# Frogduino.net
KiCad netlist of a schematic drawn in EAGLE
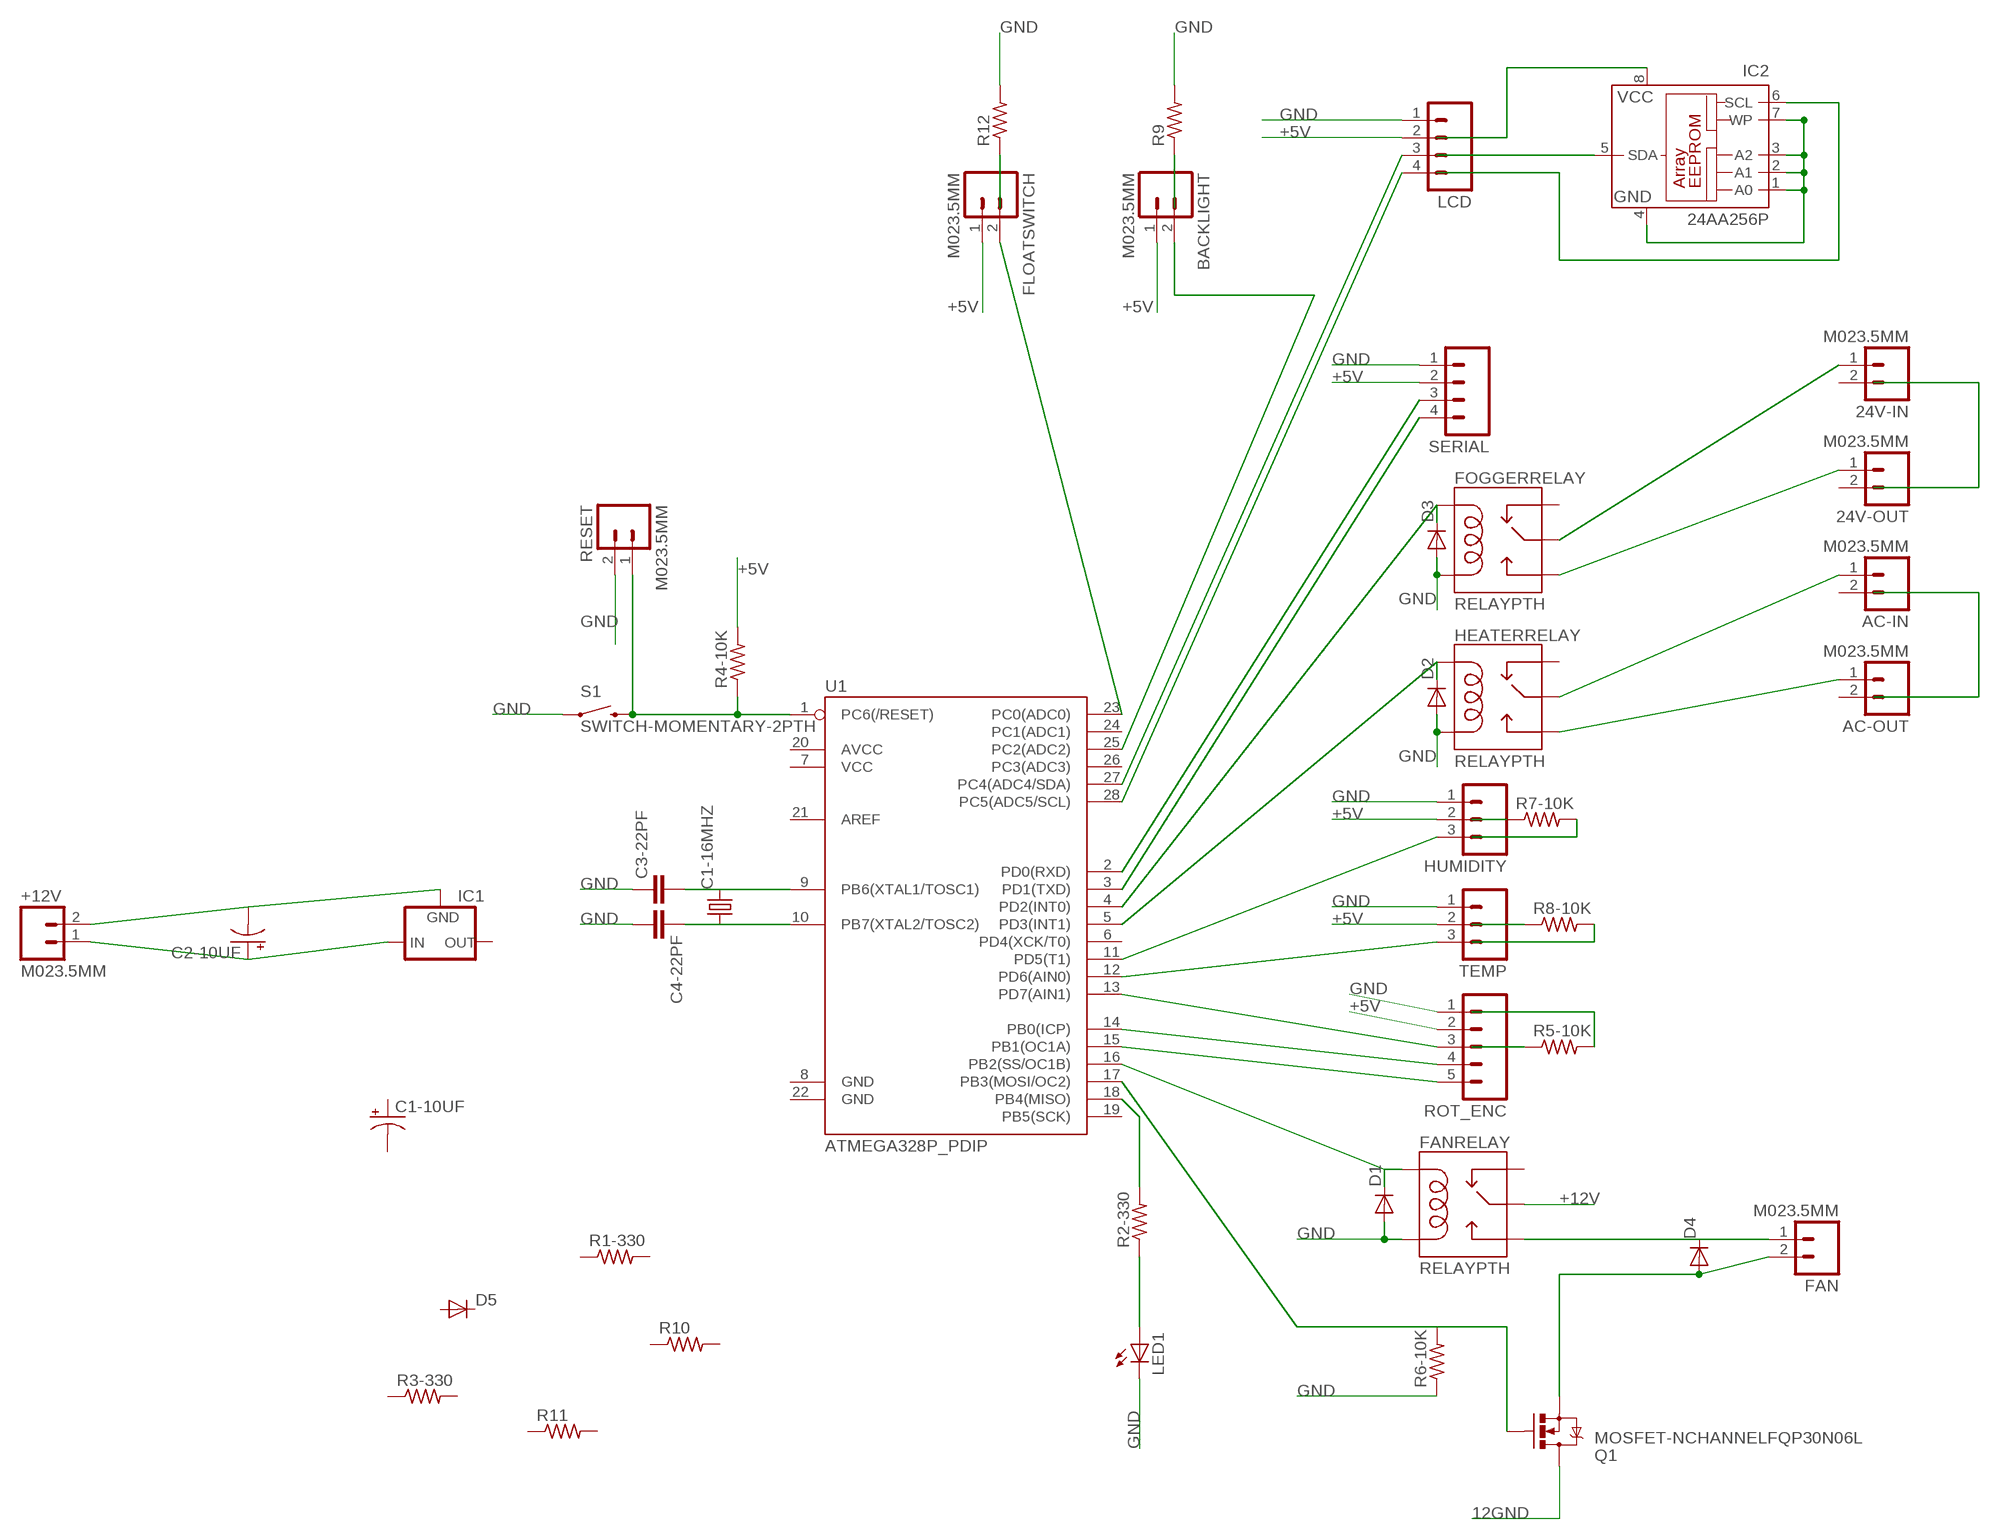
[diagram p0: schematic, sheet 1]

(export (version "E")
  (design (tool "Eeschema 10.0.6"))
  (components
    (comp (ref "+12V")
      (value "M023.5MM")
      (footprint "eagle-import:SCREWTERMINAL-3.5MM-2")
      (libsource (lib "eagle-import") (part "M023.5MM"))
    )
    (comp (ref "24V-IN")
      (value "M023.5MM")
      (footprint "eagle-import:SCREWTERMINAL-3.5MM-2")
      (libsource (lib "eagle-import") (part "M023.5MM"))
    )
    (comp (ref "24V-OUT")
      (value "M023.5MM")
      (footprint "eagle-import:SCREWTERMINAL-3.5MM-2")
      (libsource (lib "eagle-import") (part "M023.5MM"))
    )
    (comp (ref "AC-IN")
      (value "M023.5MM")
      (footprint "eagle-import:SCREWTERMINAL-3.5MM-2")
      (libsource (lib "eagle-import") (part "M023.5MM"))
    )
    (comp (ref "AC-OUT")
      (value "M023.5MM")
      (footprint "eagle-import:SCREWTERMINAL-3.5MM-2")
      (libsource (lib "eagle-import") (part "M023.5MM"))
    )
    (comp (ref "BACKLIGHT")
      (value "M023.5MM")
      (footprint "eagle-import:SCREWTERMINAL-3.5MM-2")
      (libsource (lib "eagle-import") (part "M023.5MM"))
    )
    (comp (ref "C1-10UF")
      (value "CAP_POLPTH2")
      (footprint "eagle-import:CPOL-RADIAL-10UF-25V")
      (libsource (lib "eagle-import") (part "CAP_POLPTH2"))
    )
    (comp (ref "C1-16MHZ")
      (value "CRYSTALHC49US")
      (footprint "eagle-import:HC49US")
      (libsource (lib "eagle-import") (part "CRYSTALHC49US"))
    )
    (comp (ref "C2-10UF")
      (value "CAP_POLPTH2")
      (footprint "eagle-import:CPOL-RADIAL-10UF-25V")
      (libsource (lib "eagle-import") (part "CAP_POLPTH2"))
    )
    (comp (ref "C3-22PF")
      (value "CAPKIT")
      (footprint "eagle-import:CAP-PTH-SMALL-KIT")
      (libsource (lib "eagle-import") (part "CAPKIT"))
    )
    (comp (ref "C4-22PF")
      (value "CAPKIT")
      (footprint "eagle-import:CAP-PTH-SMALL-KIT")
      (libsource (lib "eagle-import") (part "CAPKIT"))
    )
    (comp (ref "D1")
      (value "DIODEPTH")
      (footprint "eagle-import:DIODE-1N4001")
      (libsource (lib "eagle-import") (part "DIODEPTH"))
    )
    (comp (ref "D2")
      (value "DIODEPTH")
      (footprint "eagle-import:DIODE-1N4001")
      (libsource (lib "eagle-import") (part "DIODEPTH"))
    )
    (comp (ref "D3")
      (value "DIODEPTH")
      (footprint "eagle-import:DIODE-1N4001")
      (libsource (lib "eagle-import") (part "DIODEPTH"))
    )
    (comp (ref "D4")
      (value "DIODEPTH")
      (footprint "eagle-import:DIODE-1N4001")
      (libsource (lib "eagle-import") (part "DIODEPTH"))
    )
    (comp (ref "D5")
      (value "DIODEPTH")
      (footprint "eagle-import:DIODE-1N4001")
      (libsource (lib "eagle-import") (part "DIODEPTH"))
    )
    (comp (ref "FAN")
      (value "M023.5MM")
      (footprint "eagle-import:SCREWTERMINAL-3.5MM-2")
      (libsource (lib "eagle-import") (part "M023.5MM"))
    )
    (comp (ref "FANRELAY")
      (value "RELAYPTH")
      (footprint "eagle-import:RELAY-G5Q")
      (libsource (lib "eagle-import") (part "RELAYPTH"))
    )
    (comp (ref "FLOATSWITCH")
      (value "M023.5MM")
      (footprint "eagle-import:SCREWTERMINAL-3.5MM-2")
      (libsource (lib "eagle-import") (part "M023.5MM"))
    )
    (comp (ref "FOGGERRELAY")
      (value "RELAYPTH")
      (footprint "eagle-import:RELAY-G5Q")
      (libsource (lib "eagle-import") (part "RELAYPTH"))
    )
    (comp (ref "HEATERRELAY")
      (value "RELAYPTH")
      (footprint "eagle-import:RELAY-G5Q")
      (libsource (lib "eagle-import") (part "RELAYPTH"))
    )
    (comp (ref "HUMIDITY")
      (value "M03SCREW")
      (footprint "eagle-import:SCREWTERMINAL-3.5MM-3")
      (libsource (lib "eagle-import") (part "M03SCREW"))
    )
    (comp (ref "IC1")
      (value "V_REG_78XX-TO-220")
      (footprint "eagle-import:TO-220-ALT")
      (libsource (lib "eagle-import") (part "V_REG_78XX-TO-220"))
    )
    (comp (ref "IC2")
      (value "24AA256P")
      (footprint "eagle-import:DIL8")
      (fields (field (name "MF") "MICROCHIP") (field (name "MPN") "24AA256-I/P"))
      (libsource (lib "eagle-import") (part "24PAA256"))
    )
    (comp (ref "LCD")
      (value "M04PTH")
      (footprint "eagle-import:1X04")
      (libsource (lib "eagle-import") (part "M04PTH"))
    )
    (comp (ref "LED1")
      (value "LED5MM")
      (footprint "eagle-import:LED5MM")
      (libsource (lib "eagle-import") (part "LED5MM"))
    )
    (comp (ref "Q1")
      (value "MOSFET-NCHANNELFQP30N06L")
      (footprint "eagle-import:TO220V")
      (libsource (lib "eagle-import") (part "MOSFET-NCHANNELFQP30N06L"))
    )
    (comp (ref "R1-330")
      (value "R-US_0204/5")
      (footprint "eagle-import:0204_5")
      (libsource (lib "eagle-import") (part "R-US_0204/5"))
    )
    (comp (ref "R2-330")
      (value "R-US_0204/5")
      (footprint "eagle-import:0204_5")
      (libsource (lib "eagle-import") (part "R-US_0204/5"))
    )
    (comp (ref "R3-330")
      (value "R-US_0204/5")
      (footprint "eagle-import:0204_5")
      (libsource (lib "eagle-import") (part "R-US_0204/5"))
    )
    (comp (ref "R4-10K")
      (value "R-US_0204/5")
      (footprint "eagle-import:0204_5")
      (libsource (lib "eagle-import") (part "R-US_0204/5"))
    )
    (comp (ref "R5-10K")
      (value "R-US_0204/5")
      (footprint "eagle-import:0204_5")
      (libsource (lib "eagle-import") (part "R-US_0204/5"))
    )
    (comp (ref "R6-10K")
      (value "R-US_0204/5")
      (footprint "eagle-import:0204_5")
      (libsource (lib "eagle-import") (part "R-US_0204/5"))
    )
    (comp (ref "R7-10K")
      (value "R-US_0204/5")
      (footprint "eagle-import:0204_5")
      (libsource (lib "eagle-import") (part "R-US_0204/5"))
    )
    (comp (ref "R8-10K")
      (value "R-US_0204/5")
      (footprint "eagle-import:0204_5")
      (libsource (lib "eagle-import") (part "R-US_0204/5"))
    )
    (comp (ref "R9")
      (value "R-US_0204/5")
      (footprint "eagle-import:0204_5")
      (libsource (lib "eagle-import") (part "R-US_0204/5"))
    )
    (comp (ref "R10")
      (value "R-US_0204/5")
      (footprint "eagle-import:0204_5")
      (libsource (lib "eagle-import") (part "R-US_0204/5"))
    )
    (comp (ref "R11")
      (value "R-US_0204/5")
      (footprint "eagle-import:0204_5")
      (libsource (lib "eagle-import") (part "R-US_0204/5"))
    )
    (comp (ref "R12")
      (value "R-US_0204/5")
      (footprint "eagle-import:0204_5")
      (libsource (lib "eagle-import") (part "R-US_0204/5"))
    )
    (comp (ref "RESET")
      (value "M023.5MM")
      (footprint "eagle-import:SCREWTERMINAL-3.5MM-2")
      (libsource (lib "eagle-import") (part "M023.5MM"))
    )
    (comp (ref "ROT_ENC")
      (value "M05PTH")
      (footprint "eagle-import:1X05")
      (libsource (lib "eagle-import") (part "M05PTH"))
    )
    (comp (ref "S1")
      (value "SWITCH-MOMENTARY-2PTH")
      (footprint "eagle-import:TACTILE-PTH")
      (libsource (lib "eagle-import") (part "SWITCH-MOMENTARY-2PTH"))
    )
    (comp (ref "SERIAL")
      (value "M04SCREW")
      (footprint "eagle-import:SCREWTERMINAL-3.5MM-4")
      (libsource (lib "eagle-import") (part "M04SCREW"))
    )
    (comp (ref "TEMP")
      (value "M03SCREW")
      (footprint "eagle-import:SCREWTERMINAL-3.5MM-3")
      (libsource (lib "eagle-import") (part "M03SCREW"))
    )
    (comp (ref "U1")
      (value "ATMEGA328P_PDIP")
      (footprint "eagle-import:DIL28-3")
      (libsource (lib "eagle-import") (part "ATMEGA328P_PDIP"))
    )
  )
  (nets
    (net (code "1") (name "/+5V") (class "Default")
      (node (ref "BACKLIGHT") (pin "1") (pinfunction "1_1") (pintype "passive"))
      (node (ref "FLOATSWITCH") (pin "1") (pinfunction "1_1") (pintype "passive"))
      (node (ref "HUMIDITY") (pin "2") (pinfunction "2_2") (pintype "passive"))
      (node (ref "LCD") (pin "2") (pinfunction "2_2") (pintype "passive"))
      (node (ref "R4-10K") (pin "2") (pinfunction "2_2") (pintype "passive"))
      (node (ref "ROT_ENC") (pin "2") (pinfunction "2_2") (pintype "passive"))
      (node (ref "SERIAL") (pin "2") (pinfunction "2_2") (pintype "passive"))
      (node (ref "TEMP") (pin "2") (pinfunction "2_2") (pintype "passive"))
    )
    (net (code "2") (name "/+12V") (class "Default")
      (node (ref "D4") (pin "C") (pinfunction "C_C") (pintype "passive"))
      (node (ref "FAN") (pin "1") (pinfunction "1_1") (pintype "passive"))
      (node (ref "FANRELAY") (pin "2") (pinfunction "MAIN_2") (pintype "bidirectional"))
      (node (ref "FANRELAY") (pin "3") (pinfunction "NO_3") (pintype "bidirectional"))
    )
    (net (code "3") (name "/12GND") (class "Default")
      (node (ref "Q1") (pin "2") (pinfunction "D_2") (pintype "passive"))
    )
    (net (code "4") (name "/GND") (class "Default")
      (node (ref "C3-22PF") (pin "1") (pinfunction "1_1") (pintype "passive"))
      (node (ref "C4-22PF") (pin "2") (pinfunction "2_2") (pintype "passive"))
      (node (ref "D1") (pin "A") (pinfunction "A_A") (pintype "passive"))
      (node (ref "D2") (pin "A") (pinfunction "A_A") (pintype "passive"))
      (node (ref "D3") (pin "A") (pinfunction "A_A") (pintype "passive"))
      (node (ref "FANRELAY") (pin "1") (pinfunction "COIL2_1") (pintype "bidirectional"))
      (node (ref "FOGGERRELAY") (pin "1") (pinfunction "COIL2_1") (pintype "bidirectional"))
      (node (ref "HEATERRELAY") (pin "1") (pinfunction "COIL2_1") (pintype "bidirectional"))
      (node (ref "HUMIDITY") (pin "1") (pinfunction "1_1") (pintype "passive"))
      (node (ref "LCD") (pin "1") (pinfunction "1_1") (pintype "passive"))
      (node (ref "LED1") (pin "K") (pinfunction "C_K") (pintype "passive"))
      (node (ref "R12") (pin "2") (pinfunction "2_2") (pintype "passive"))
      (node (ref "R6-10K") (pin "1") (pinfunction "1_1") (pintype "passive"))
      (node (ref "R9") (pin "2") (pinfunction "2_2") (pintype "passive"))
      (node (ref "RESET") (pin "2") (pinfunction "2_2") (pintype "passive"))
      (node (ref "ROT_ENC") (pin "1") (pinfunction "1_1") (pintype "passive"))
      (node (ref "S1") (pin "1") (pinfunction "1_1") (pintype "passive"))
      (node (ref "SERIAL") (pin "1") (pinfunction "1_1") (pintype "passive"))
      (node (ref "TEMP") (pin "1") (pinfunction "1_1") (pintype "passive"))
    )
    (net (code "5") (name "Net-(C2-10UF-+)") (class "Default")
      (node (ref "+12V") (pin "1") (pinfunction "1_1") (pintype "passive"))
      (node (ref "C2-10UF") (pin "1") (pinfunction "+_1") (pintype "passive"))
      (node (ref "IC1") (pin "IN") (pinfunction "IN_IN") (pintype "input"))
    )
    (net (code "6") (name "Net-(C2-10UF--)") (class "Default")
      (node (ref "+12V") (pin "2") (pinfunction "2_2") (pintype "passive"))
      (node (ref "C2-10UF") (pin "2") (pinfunction "-_2") (pintype "passive"))
      (node (ref "IC1") (pin "GND") (pinfunction "GND_GND") (pintype "input"))
    )
    (net (code "7") (name "Net-(FANRELAY-COIL1)") (class "Default")
      (node (ref "D1") (pin "C") (pinfunction "C_C") (pintype "passive"))
      (node (ref "FANRELAY") (pin "5") (pinfunction "COIL1_5") (pintype "bidirectional"))
      (node (ref "U1") (pin "16") (pinfunction "PB2(SS/OC1B)_16") (pintype "bidirectional"))
    )
    (net (code "8") (name "Net-(FOGGERRELAY-COIL1)") (class "Default")
      (node (ref "D3") (pin "C") (pinfunction "C_C") (pintype "passive"))
      (node (ref "FOGGERRELAY") (pin "5") (pinfunction "COIL1_5") (pintype "bidirectional"))
      (node (ref "U1") (pin "4") (pinfunction "PD2(INT0)_4") (pintype "bidirectional"))
    )
    (net (code "9") (name "Net-(FOGGERRELAY-MAIN)") (class "Default")
      (node (ref "24V-IN") (pin "1") (pinfunction "1_1") (pintype "passive"))
      (node (ref "FOGGERRELAY") (pin "2") (pinfunction "MAIN_2") (pintype "bidirectional"))
    )
    (net (code "10") (name "Net-(FOGGERRELAY-NO)") (class "Default")
      (node (ref "24V-OUT") (pin "1") (pinfunction "1_1") (pintype "passive"))
      (node (ref "FOGGERRELAY") (pin "3") (pinfunction "NO_3") (pintype "bidirectional"))
    )
    (net (code "11") (name "Net-(HEATERRELAY-COIL1)") (class "Default")
      (node (ref "D2") (pin "C") (pinfunction "C_C") (pintype "passive"))
      (node (ref "HEATERRELAY") (pin "5") (pinfunction "COIL1_5") (pintype "bidirectional"))
      (node (ref "U1") (pin "5") (pinfunction "PD3(INT1)_5") (pintype "bidirectional"))
    )
    (net (code "12") (name "Net-(HEATERRELAY-MAIN)") (class "Default")
      (node (ref "AC-IN") (pin "1") (pinfunction "1_1") (pintype "passive"))
      (node (ref "HEATERRELAY") (pin "2") (pinfunction "MAIN_2") (pintype "bidirectional"))
    )
    (net (code "13") (name "Net-(HEATERRELAY-NO)") (class "Default")
      (node (ref "AC-OUT") (pin "1") (pinfunction "1_1") (pintype "passive"))
      (node (ref "HEATERRELAY") (pin "3") (pinfunction "NO_3") (pintype "bidirectional"))
    )
    (net (code "14") (name "Net-(IC2-A0)") (class "Default")
      (node (ref "IC2") (pin "1") (pinfunction "A0_1") (pintype "input"))
      (node (ref "IC2") (pin "2") (pinfunction "A1_2") (pintype "input"))
      (node (ref "IC2") (pin "3") (pinfunction "A2_3") (pintype "input"))
      (node (ref "IC2") (pin "4") (pinfunction "GND_4") (pintype "power_in"))
      (node (ref "IC2") (pin "7") (pinfunction "WP_7") (pintype "input"))
    )
    (net (code "15") (name "Net-(LED1-PadA)") (class "Default")
      (node (ref "LED1") (pin "A") (pinfunction "A_A") (pintype "passive"))
      (node (ref "R2-330") (pin "1") (pinfunction "1_1") (pintype "passive"))
    )
    (net (code "16") (name "Net-(Q1-G)") (class "Default")
      (node (ref "Q1") (pin "1") (pinfunction "G_1") (pintype "passive"))
      (node (ref "R6-10K") (pin "2") (pinfunction "2_2") (pintype "passive"))
      (node (ref "U1") (pin "17") (pinfunction "PB3(MOSI/OC2)_17") (pintype "bidirectional"))
    )
    (net (code "17") (name "Net-(Q1-S)") (class "Default")
      (node (ref "D4") (pin "A") (pinfunction "A_A") (pintype "passive"))
      (node (ref "FAN") (pin "2") (pinfunction "2_2") (pintype "passive"))
      (node (ref "Q1") (pin "3") (pinfunction "S_3") (pintype "passive"))
    )
    (net (code "18") (name "Net-(S1-2)") (class "Default")
      (node (ref "R4-10K") (pin "1") (pinfunction "1_1") (pintype "passive"))
      (node (ref "RESET") (pin "1") (pinfunction "1_1") (pintype "passive"))
      (node (ref "S1") (pin "3") (pinfunction "2_3") (pintype "passive"))
      (node (ref "U1") (pin "1") (pinfunction "PC6(/RESET)_1") (pintype "bidirectional"))
    )
    (net (code "19") (name "Net-(U1-PB0(ICP))") (class "Default")
      (node (ref "ROT_ENC") (pin "4") (pinfunction "4_4") (pintype "passive"))
      (node (ref "U1") (pin "14") (pinfunction "PB0(ICP)_14") (pintype "bidirectional"))
    )
    (net (code "20") (name "Net-(U1-PB1(OC1A))") (class "Default")
      (node (ref "ROT_ENC") (pin "5") (pinfunction "5_5") (pintype "passive"))
      (node (ref "U1") (pin "15") (pinfunction "PB1(OC1A)_15") (pintype "bidirectional"))
    )
    (net (code "21") (name "Net-(U1-PB4(MISO))") (class "Default")
      (node (ref "R2-330") (pin "2") (pinfunction "2_2") (pintype "passive"))
      (node (ref "U1") (pin "18") (pinfunction "PB4(MISO)_18") (pintype "bidirectional"))
    )
    (net (code "22") (name "Net-(U1-PB6(XTAL1{slash}TOSC1))") (class "Default")
      (node (ref "C1-16MHZ") (pin "2") (pinfunction "2_2") (pintype "passive"))
      (node (ref "C3-22PF") (pin "2") (pinfunction "2_2") (pintype "passive"))
      (node (ref "U1") (pin "9") (pinfunction "PB6(XTAL1/TOSC1)_9") (pintype "bidirectional"))
    )
    (net (code "23") (name "Net-(U1-PB7(XTAL2{slash}TOSC2))") (class "Default")
      (node (ref "C1-16MHZ") (pin "1") (pinfunction "1_1") (pintype "passive"))
      (node (ref "C4-22PF") (pin "1") (pinfunction "1_1") (pintype "passive"))
      (node (ref "U1") (pin "10") (pinfunction "PB7(XTAL2/TOSC2)_10") (pintype "bidirectional"))
    )
    (net (code "24") (name "Net-(U1-PC0(ADC0))") (class "Default")
      (node (ref "FLOATSWITCH") (pin "2") (pinfunction "2_2") (pintype "passive"))
      (node (ref "U1") (pin "23") (pinfunction "PC0(ADC0)_23") (pintype "bidirectional"))
    )
    (net (code "25") (name "Net-(U1-PC2(ADC2))") (class "Default")
      (node (ref "BACKLIGHT") (pin "2") (pinfunction "2_2") (pintype "passive"))
      (node (ref "U1") (pin "25") (pinfunction "PC2(ADC2)_25") (pintype "bidirectional"))
    )
    (net (code "26") (name "Net-(U1-PC4(ADC4{slash}SDA))") (class "Default")
      (node (ref "LCD") (pin "3") (pinfunction "3_3") (pintype "passive"))
      (node (ref "U1") (pin "27") (pinfunction "PC4(ADC4/SDA)_27") (pintype "bidirectional"))
    )
    (net (code "27") (name "Net-(U1-PC5(ADC5{slash}SCL))") (class "Default")
      (node (ref "LCD") (pin "4") (pinfunction "4_4") (pintype "passive"))
      (node (ref "U1") (pin "28") (pinfunction "PC5(ADC5/SCL)_28") (pintype "bidirectional"))
    )
    (net (code "28") (name "Net-(U1-PD0(RXD))") (class "Default")
      (node (ref "SERIAL") (pin "3") (pinfunction "3_3") (pintype "passive"))
      (node (ref "U1") (pin "2") (pinfunction "PD0(RXD)_2") (pintype "bidirectional"))
    )
    (net (code "29") (name "Net-(U1-PD1(TXD))") (class "Default")
      (node (ref "SERIAL") (pin "4") (pinfunction "4_4") (pintype "passive"))
      (node (ref "U1") (pin "3") (pinfunction "PD1(TXD)_3") (pintype "bidirectional"))
    )
    (net (code "30") (name "Net-(U1-PD5(T1))") (class "Default")
      (node (ref "HUMIDITY") (pin "3") (pinfunction "3_3") (pintype "passive"))
      (node (ref "U1") (pin "11") (pinfunction "PD5(T1)_11") (pintype "bidirectional"))
    )
    (net (code "31") (name "Net-(U1-PD6(AIN0))") (class "Default")
      (node (ref "TEMP") (pin "3") (pinfunction "3_3") (pintype "passive"))
      (node (ref "U1") (pin "12") (pinfunction "PD6(AIN0)_12") (pintype "bidirectional"))
    )
    (net (code "32") (name "Net-(U1-PD7(AIN1))") (class "Default")
      (node (ref "ROT_ENC") (pin "3") (pinfunction "3_3") (pintype "passive"))
      (node (ref "U1") (pin "13") (pinfunction "PD7(AIN1)_13") (pintype "bidirectional"))
    )
    (net (code "33") (name "unconnected-(24V-IN-Pad2)") (class "Default")
      (node (ref "24V-IN") (pin "2") (pinfunction "2_2") (pintype "passive"))
    )
    (net (code "34") (name "unconnected-(24V-OUT-Pad2)") (class "Default")
      (node (ref "24V-OUT") (pin "2") (pinfunction "2_2") (pintype "passive"))
    )
    (net (code "35") (name "unconnected-(AC-IN-Pad2)") (class "Default")
      (node (ref "AC-IN") (pin "2") (pinfunction "2_2") (pintype "passive"))
    )
    (net (code "36") (name "unconnected-(AC-OUT-Pad2)") (class "Default")
      (node (ref "AC-OUT") (pin "2") (pinfunction "2_2") (pintype "passive"))
    )
    (net (code "37") (name "unconnected-(C1-10UF-+-Pad1)") (class "Default")
      (node (ref "C1-10UF") (pin "1") (pinfunction "+_1") (pintype "passive"))
    )
    (net (code "38") (name "unconnected-(C1-10UF---Pad2)") (class "Default")
      (node (ref "C1-10UF") (pin "2") (pinfunction "-_2") (pintype "passive"))
    )
    (net (code "39") (name "unconnected-(D5-PadA)") (class "Default")
      (node (ref "D5") (pin "A") (pinfunction "A_A") (pintype "passive"))
    )
    (net (code "40") (name "unconnected-(D5-PadC)") (class "Default")
      (node (ref "D5") (pin "C") (pinfunction "C_C") (pintype "passive"))
    )
    (net (code "41") (name "unconnected-(FANRELAY-NC-Pad4)") (class "Default")
      (node (ref "FANRELAY") (pin "4") (pinfunction "NC_4") (pintype "bidirectional"))
    )
    (net (code "42") (name "unconnected-(FOGGERRELAY-NC-Pad4)") (class "Default")
      (node (ref "FOGGERRELAY") (pin "4") (pinfunction "NC_4") (pintype "bidirectional"))
    )
    (net (code "43") (name "unconnected-(HEATERRELAY-NC-Pad4)") (class "Default")
      (node (ref "HEATERRELAY") (pin "4") (pinfunction "NC_4") (pintype "bidirectional"))
    )
    (net (code "44") (name "unconnected-(IC1-PadOUT)") (class "Default")
      (node (ref "IC1") (pin "OUT") (pinfunction "OUT_OUT") (pintype "output"))
    )
    (net (code "45") (name "unconnected-(IC2-SCL-Pad6)") (class "Default")
      (node (ref "IC2") (pin "6") (pinfunction "SCL_6") (pintype "input"))
    )
    (net (code "46") (name "unconnected-(IC2-SDA-Pad5)") (class "Default")
      (node (ref "IC2") (pin "5") (pinfunction "SDA_5") (pintype "bidirectional"))
    )
    (net (code "47") (name "unconnected-(IC2-VCC-Pad8)") (class "Default")
      (node (ref "IC2") (pin "8") (pinfunction "VCC_8") (pintype "power_in"))
    )
    (net (code "48") (name "unconnected-(R1-330-Pad1)") (class "Default")
      (node (ref "R1-330") (pin "1") (pinfunction "1_1") (pintype "passive"))
    )
    (net (code "49") (name "unconnected-(R1-330-Pad2)") (class "Default")
      (node (ref "R1-330") (pin "2") (pinfunction "2_2") (pintype "passive"))
    )
    (net (code "50") (name "unconnected-(R3-330-Pad1)") (class "Default")
      (node (ref "R3-330") (pin "1") (pinfunction "1_1") (pintype "passive"))
    )
    (net (code "51") (name "unconnected-(R3-330-Pad2)") (class "Default")
      (node (ref "R3-330") (pin "2") (pinfunction "2_2") (pintype "passive"))
    )
    (net (code "52") (name "unconnected-(R5-10K-Pad1)") (class "Default")
      (node (ref "R5-10K") (pin "1") (pinfunction "1_1") (pintype "passive"))
    )
    (net (code "53") (name "unconnected-(R5-10K-Pad2)") (class "Default")
      (node (ref "R5-10K") (pin "2") (pinfunction "2_2") (pintype "passive"))
    )
    (net (code "54") (name "unconnected-(R7-10K-Pad1)") (class "Default")
      (node (ref "R7-10K") (pin "1") (pinfunction "1_1") (pintype "passive"))
    )
    (net (code "55") (name "unconnected-(R7-10K-Pad2)") (class "Default")
      (node (ref "R7-10K") (pin "2") (pinfunction "2_2") (pintype "passive"))
    )
    (net (code "56") (name "unconnected-(R8-10K-Pad1)") (class "Default")
      (node (ref "R8-10K") (pin "1") (pinfunction "1_1") (pintype "passive"))
    )
    (net (code "57") (name "unconnected-(R8-10K-Pad2)") (class "Default")
      (node (ref "R8-10K") (pin "2") (pinfunction "2_2") (pintype "passive"))
    )
    (net (code "58") (name "unconnected-(R9-Pad1)") (class "Default")
      (node (ref "R9") (pin "1") (pinfunction "1_1") (pintype "passive"))
    )
    (net (code "59") (name "unconnected-(R10-Pad1)") (class "Default")
      (node (ref "R10") (pin "1") (pinfunction "1_1") (pintype "passive"))
    )
    (net (code "60") (name "unconnected-(R10-Pad2)") (class "Default")
      (node (ref "R10") (pin "2") (pinfunction "2_2") (pintype "passive"))
    )
    (net (code "61") (name "unconnected-(R11-Pad1)") (class "Default")
      (node (ref "R11") (pin "1") (pinfunction "1_1") (pintype "passive"))
    )
    (net (code "62") (name "unconnected-(R11-Pad2)") (class "Default")
      (node (ref "R11") (pin "2") (pinfunction "2_2") (pintype "passive"))
    )
    (net (code "63") (name "unconnected-(R12-Pad1)") (class "Default")
      (node (ref "R12") (pin "1") (pinfunction "1_1") (pintype "passive"))
    )
    (net (code "64") (name "unconnected-(U1-AREF-Pad21)") (class "Default")
      (node (ref "U1") (pin "21") (pinfunction "AREF_21") (pintype "bidirectional"))
    )
    (net (code "65") (name "unconnected-(U1-AVCC-Pad20)") (class "Default")
      (node (ref "U1") (pin "20") (pinfunction "AVCC_20") (pintype "bidirectional"))
    )
    (net (code "66") (name "unconnected-(U1-GND-Pad8)") (class "Default")
      (node (ref "U1") (pin "8") (pinfunction "GND_8") (pintype "bidirectional"))
    )
    (net (code "67") (name "unconnected-(U1-GND-Pad22)") (class "Default")
      (node (ref "U1") (pin "22") (pinfunction "GND_22") (pintype "bidirectional"))
    )
    (net (code "68") (name "unconnected-(U1-PB5(SCK)-Pad19)") (class "Default")
      (node (ref "U1") (pin "19") (pinfunction "PB5(SCK)_19") (pintype "bidirectional"))
    )
    (net (code "69") (name "unconnected-(U1-PC1(ADC1)-Pad24)") (class "Default")
      (node (ref "U1") (pin "24") (pinfunction "PC1(ADC1)_24") (pintype "bidirectional"))
    )
    (net (code "70") (name "unconnected-(U1-PC3(ADC3)-Pad26)") (class "Default")
      (node (ref "U1") (pin "26") (pinfunction "PC3(ADC3)_26") (pintype "bidirectional"))
    )
    (net (code "71") (name "unconnected-(U1-PD4(XCK{slash}T0)-Pad6)") (class "Default")
      (node (ref "U1") (pin "6") (pinfunction "PD4(XCK/T0)_6") (pintype "bidirectional"))
    )
    (net (code "72") (name "unconnected-(U1-VCC-Pad7)") (class "Default")
      (node (ref "U1") (pin "7") (pinfunction "VCC_7") (pintype "bidirectional"))
    )
  )
)
